# buck_converter.net
KiCad netlist of a schematic drawn in EAGLE
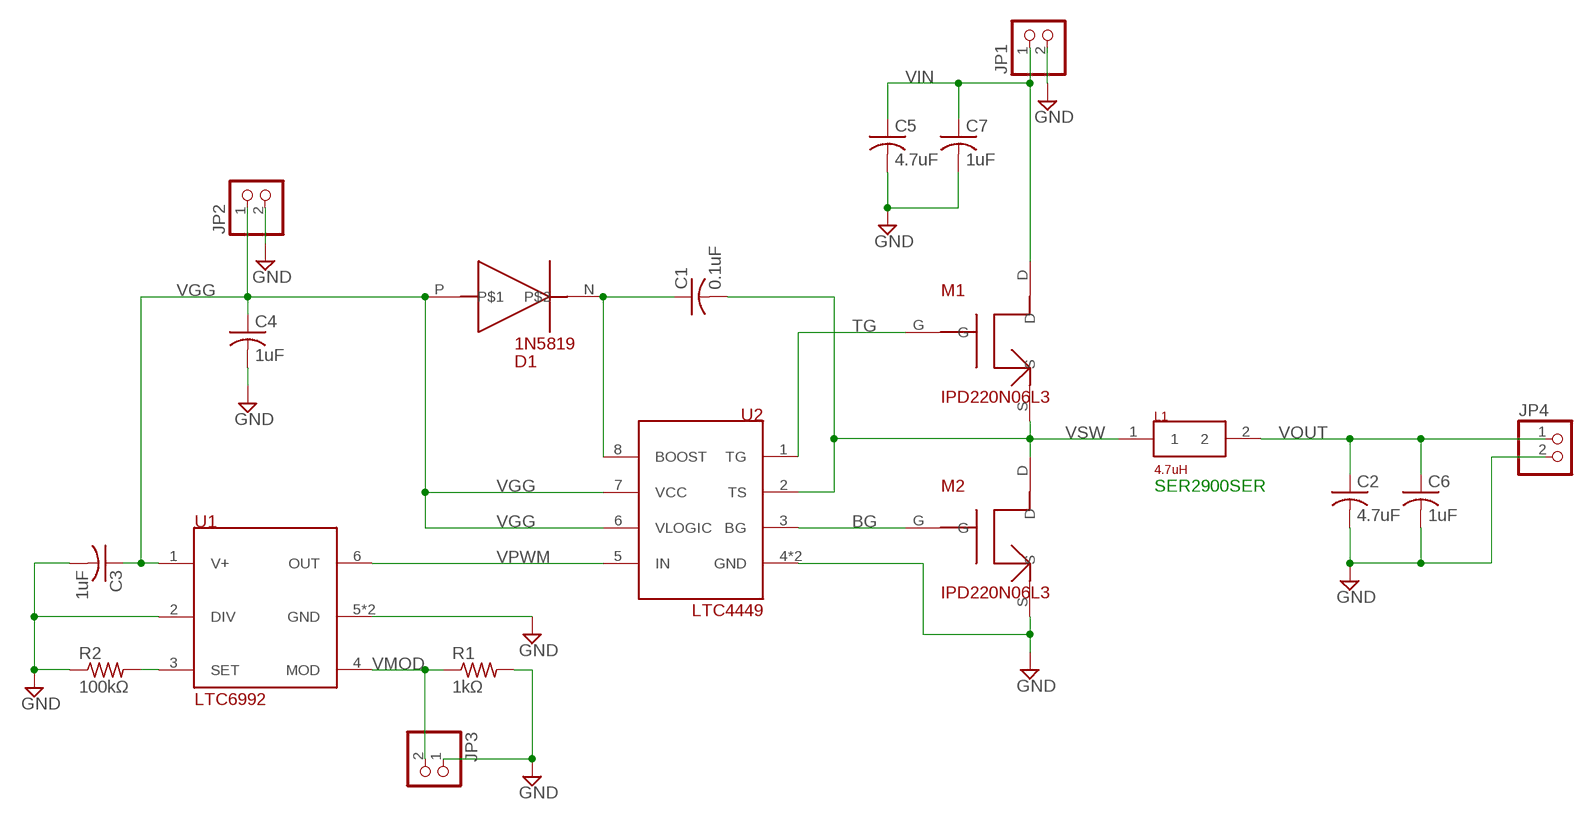
[diagram p0: schematic, sheet 1]

(export (version "E")
  (design (tool "Eeschema 10.0.6"))
  (components
    (comp (ref "C1")
      (value "0.1uF")
      (footprint "eagle-import:C0805")
      (libsource (lib "eagle-import") (part "C-US"))
    )
    (comp (ref "C2")
      (value "4.7uF")
      (footprint "eagle-import:C1206")
      (libsource (lib "eagle-import") (part "C-USC1206"))
    )
    (comp (ref "C3")
      (value "1uF")
      (footprint "eagle-import:C0805")
      (libsource (lib "eagle-import") (part "C-US"))
    )
    (comp (ref "C4")
      (value "1uF")
      (footprint "eagle-import:C0805")
      (libsource (lib "eagle-import") (part "C-US"))
    )
    (comp (ref "C5")
      (value "4.7uF")
      (footprint "eagle-import:C1206")
      (libsource (lib "eagle-import") (part "C-USC1206"))
    )
    (comp (ref "C6")
      (value "1uF")
      (footprint "eagle-import:C0805")
      (libsource (lib "eagle-import") (part "C-US"))
    )
    (comp (ref "C7")
      (value "1uF")
      (footprint "eagle-import:C0805")
      (libsource (lib "eagle-import") (part "C-US"))
    )
    (comp (ref "D1")
      (value "1N5819")
      (footprint "eagle-import:SOD123")
      (libsource (lib "eagle-import") (part "DIODE"))
    )
    (comp (ref "JP1")
      (value "PINHD-1X2")
      (footprint "eagle-import:1X02")
      (libsource (lib "eagle-import") (part "PINHD-1X2"))
    )
    (comp (ref "JP2")
      (value "PINHD-1X2")
      (footprint "eagle-import:1X02")
      (libsource (lib "eagle-import") (part "PINHD-1X2"))
    )
    (comp (ref "JP3")
      (value "PINHD-1X2")
      (footprint "eagle-import:1X02")
      (libsource (lib "eagle-import") (part "PINHD-1X2"))
    )
    (comp (ref "JP4")
      (value "PINHD-1X2")
      (footprint "eagle-import:1X02")
      (libsource (lib "eagle-import") (part "PINHD-1X2"))
    )
    (comp (ref "L1")
      (value "4.7uH")
      (footprint "eagle-import:SER2900")
      (libsource (lib "eagle-import") (part "SER2900SER"))
    )
    (comp (ref "M1")
      (value "IPD220N06L3")
      (footprint "eagle-import:DPAK")
      (libsource (lib "eagle-import") (part "MOSFET_DPAK"))
    )
    (comp (ref "M2")
      (value "IPD220N06L3")
      (footprint "eagle-import:DPAK")
      (libsource (lib "eagle-import") (part "MOSFET_DPAK"))
    )
    (comp (ref "R1")
      (value "1kΩ")
      (footprint "eagle-import:R0805")
      (libsource (lib "eagle-import") (part "R-US"))
    )
    (comp (ref "R2")
      (value "100kΩ")
      (footprint "eagle-import:R0805")
      (libsource (lib "eagle-import") (part "R-US"))
    )
    (comp (ref "U1")
      (value "LTC6992")
      (footprint "eagle-import:LTC6992")
      (libsource (lib "eagle-import") (part "LTC6992"))
    )
    (comp (ref "U2")
      (value "LTC4449")
      (footprint "eagle-import:DCB8")
      (libsource (lib "eagle-import") (part "LTC4449"))
    )
  )
  (nets
    (net (code "1") (name "/BG") (class "Default")
      (node (ref "M2") (pin "G") (pinfunction "G_G") (pintype "bidirectional"))
      (node (ref "U2") (pin "3") (pinfunction "BG_3") (pintype "bidirectional"))
    )
    (net (code "2") (name "/TG") (class "Default")
      (node (ref "M1") (pin "G") (pinfunction "G_G") (pintype "bidirectional"))
      (node (ref "U2") (pin "1") (pinfunction "TG_1") (pintype "bidirectional"))
    )
    (net (code "3") (name "/VGG") (class "Default")
      (node (ref "C3") (pin "1") (pinfunction "1_1") (pintype "passive"))
      (node (ref "C4") (pin "1") (pinfunction "1_1") (pintype "passive"))
      (node (ref "D1") (pin "P") (pinfunction "P$1_P") (pintype "bidirectional"))
      (node (ref "JP2") (pin "1") (pinfunction "1_1") (pintype "passive"))
      (node (ref "U1") (pin "1") (pinfunction "V+_1") (pintype "bidirectional"))
      (node (ref "U2") (pin "6") (pinfunction "VLOGIC_6") (pintype "bidirectional"))
      (node (ref "U2") (pin "7") (pinfunction "VCC_7") (pintype "bidirectional"))
    )
    (net (code "4") (name "/VIN") (class "Default")
      (node (ref "C5") (pin "1") (pinfunction "1_1") (pintype "passive"))
      (node (ref "C7") (pin "1") (pinfunction "1_1") (pintype "passive"))
      (node (ref "JP1") (pin "1") (pinfunction "1_1") (pintype "passive"))
      (node (ref "M1") (pin "D") (pinfunction "D_D") (pintype "bidirectional"))
    )
    (net (code "5") (name "/VMOD") (class "Default")
      (node (ref "JP3") (pin "2") (pinfunction "2_2") (pintype "passive"))
      (node (ref "R1") (pin "1") (pinfunction "1_1") (pintype "passive"))
      (node (ref "U1") (pin "4") (pinfunction "MOD_4") (pintype "bidirectional"))
    )
    (net (code "6") (name "/VOUT") (class "Default")
      (node (ref "C2") (pin "1") (pinfunction "1_1") (pintype "passive"))
      (node (ref "C6") (pin "1") (pinfunction "1_1") (pintype "passive"))
      (node (ref "JP4") (pin "1") (pinfunction "1_1") (pintype "passive"))
      (node (ref "L1") (pin "2") (pinfunction "2_2") (pintype "bidirectional"))
    )
    (net (code "7") (name "/VPWM") (class "Default")
      (node (ref "U1") (pin "6") (pinfunction "OUT_6") (pintype "bidirectional"))
      (node (ref "U2") (pin "5") (pinfunction "IN_5") (pintype "bidirectional"))
    )
    (net (code "8") (name "/VSW") (class "Default")
      (node (ref "C1") (pin "2") (pinfunction "2_2") (pintype "passive"))
      (node (ref "L1") (pin "1") (pinfunction "1_1") (pintype "bidirectional"))
      (node (ref "M1") (pin "S") (pinfunction "S_S") (pintype "bidirectional"))
      (node (ref "M2") (pin "D") (pinfunction "D_D") (pintype "bidirectional"))
      (node (ref "U2") (pin "2") (pinfunction "TS_2") (pintype "bidirectional"))
    )
    (net (code "9") (name "GND") (class "Default")
      (node (ref "C2") (pin "2") (pinfunction "2_2") (pintype "passive"))
      (node (ref "C3") (pin "2") (pinfunction "2_2") (pintype "passive"))
      (node (ref "C4") (pin "2") (pinfunction "2_2") (pintype "passive"))
      (node (ref "C5") (pin "2") (pinfunction "2_2") (pintype "passive"))
      (node (ref "C6") (pin "2") (pinfunction "2_2") (pintype "passive"))
      (node (ref "C7") (pin "2") (pinfunction "2_2") (pintype "passive"))
      (node (ref "JP1") (pin "2") (pinfunction "2_2") (pintype "passive"))
      (node (ref "JP2") (pin "2") (pinfunction "2_2") (pintype "passive"))
      (node (ref "JP3") (pin "1") (pinfunction "1_1") (pintype "passive"))
      (node (ref "JP4") (pin "2") (pinfunction "2_2") (pintype "passive"))
      (node (ref "M2") (pin "S") (pinfunction "S_S") (pintype "bidirectional"))
      (node (ref "R1") (pin "2") (pinfunction "2_2") (pintype "passive"))
      (node (ref "R2") (pin "1") (pinfunction "1_1") (pintype "passive"))
      (node (ref "U1") (pin "2") (pinfunction "DIV_2") (pintype "bidirectional"))
      (node (ref "U1") (pin "5") (pinfunction "GND_5") (pintype "bidirectional"))
      (node (ref "U1") (pin "7") (pinfunction "GND_7") (pintype "bidirectional"))
      (node (ref "U2") (pin "4") (pinfunction "GND_4") (pintype "bidirectional"))
      (node (ref "U2") (pin "9") (pinfunction "GND_9") (pintype "bidirectional"))
    )
    (net (code "10") (name "Net-(D1-P$2)") (class "Default")
      (node (ref "C1") (pin "1") (pinfunction "1_1") (pintype "passive"))
      (node (ref "D1") (pin "N") (pinfunction "P$2_N") (pintype "bidirectional"))
      (node (ref "U2") (pin "8") (pinfunction "BOOST_8") (pintype "bidirectional"))
    )
    (net (code "11") (name "Net-(U1-SET)") (class "Default")
      (node (ref "R2") (pin "2") (pinfunction "2_2") (pintype "passive"))
      (node (ref "U1") (pin "3") (pinfunction "SET_3") (pintype "bidirectional"))
    )
  )
)
